# EasyEDA-wega-mixer.net
KiCad netlist of a schematic drawn in EasyEDA
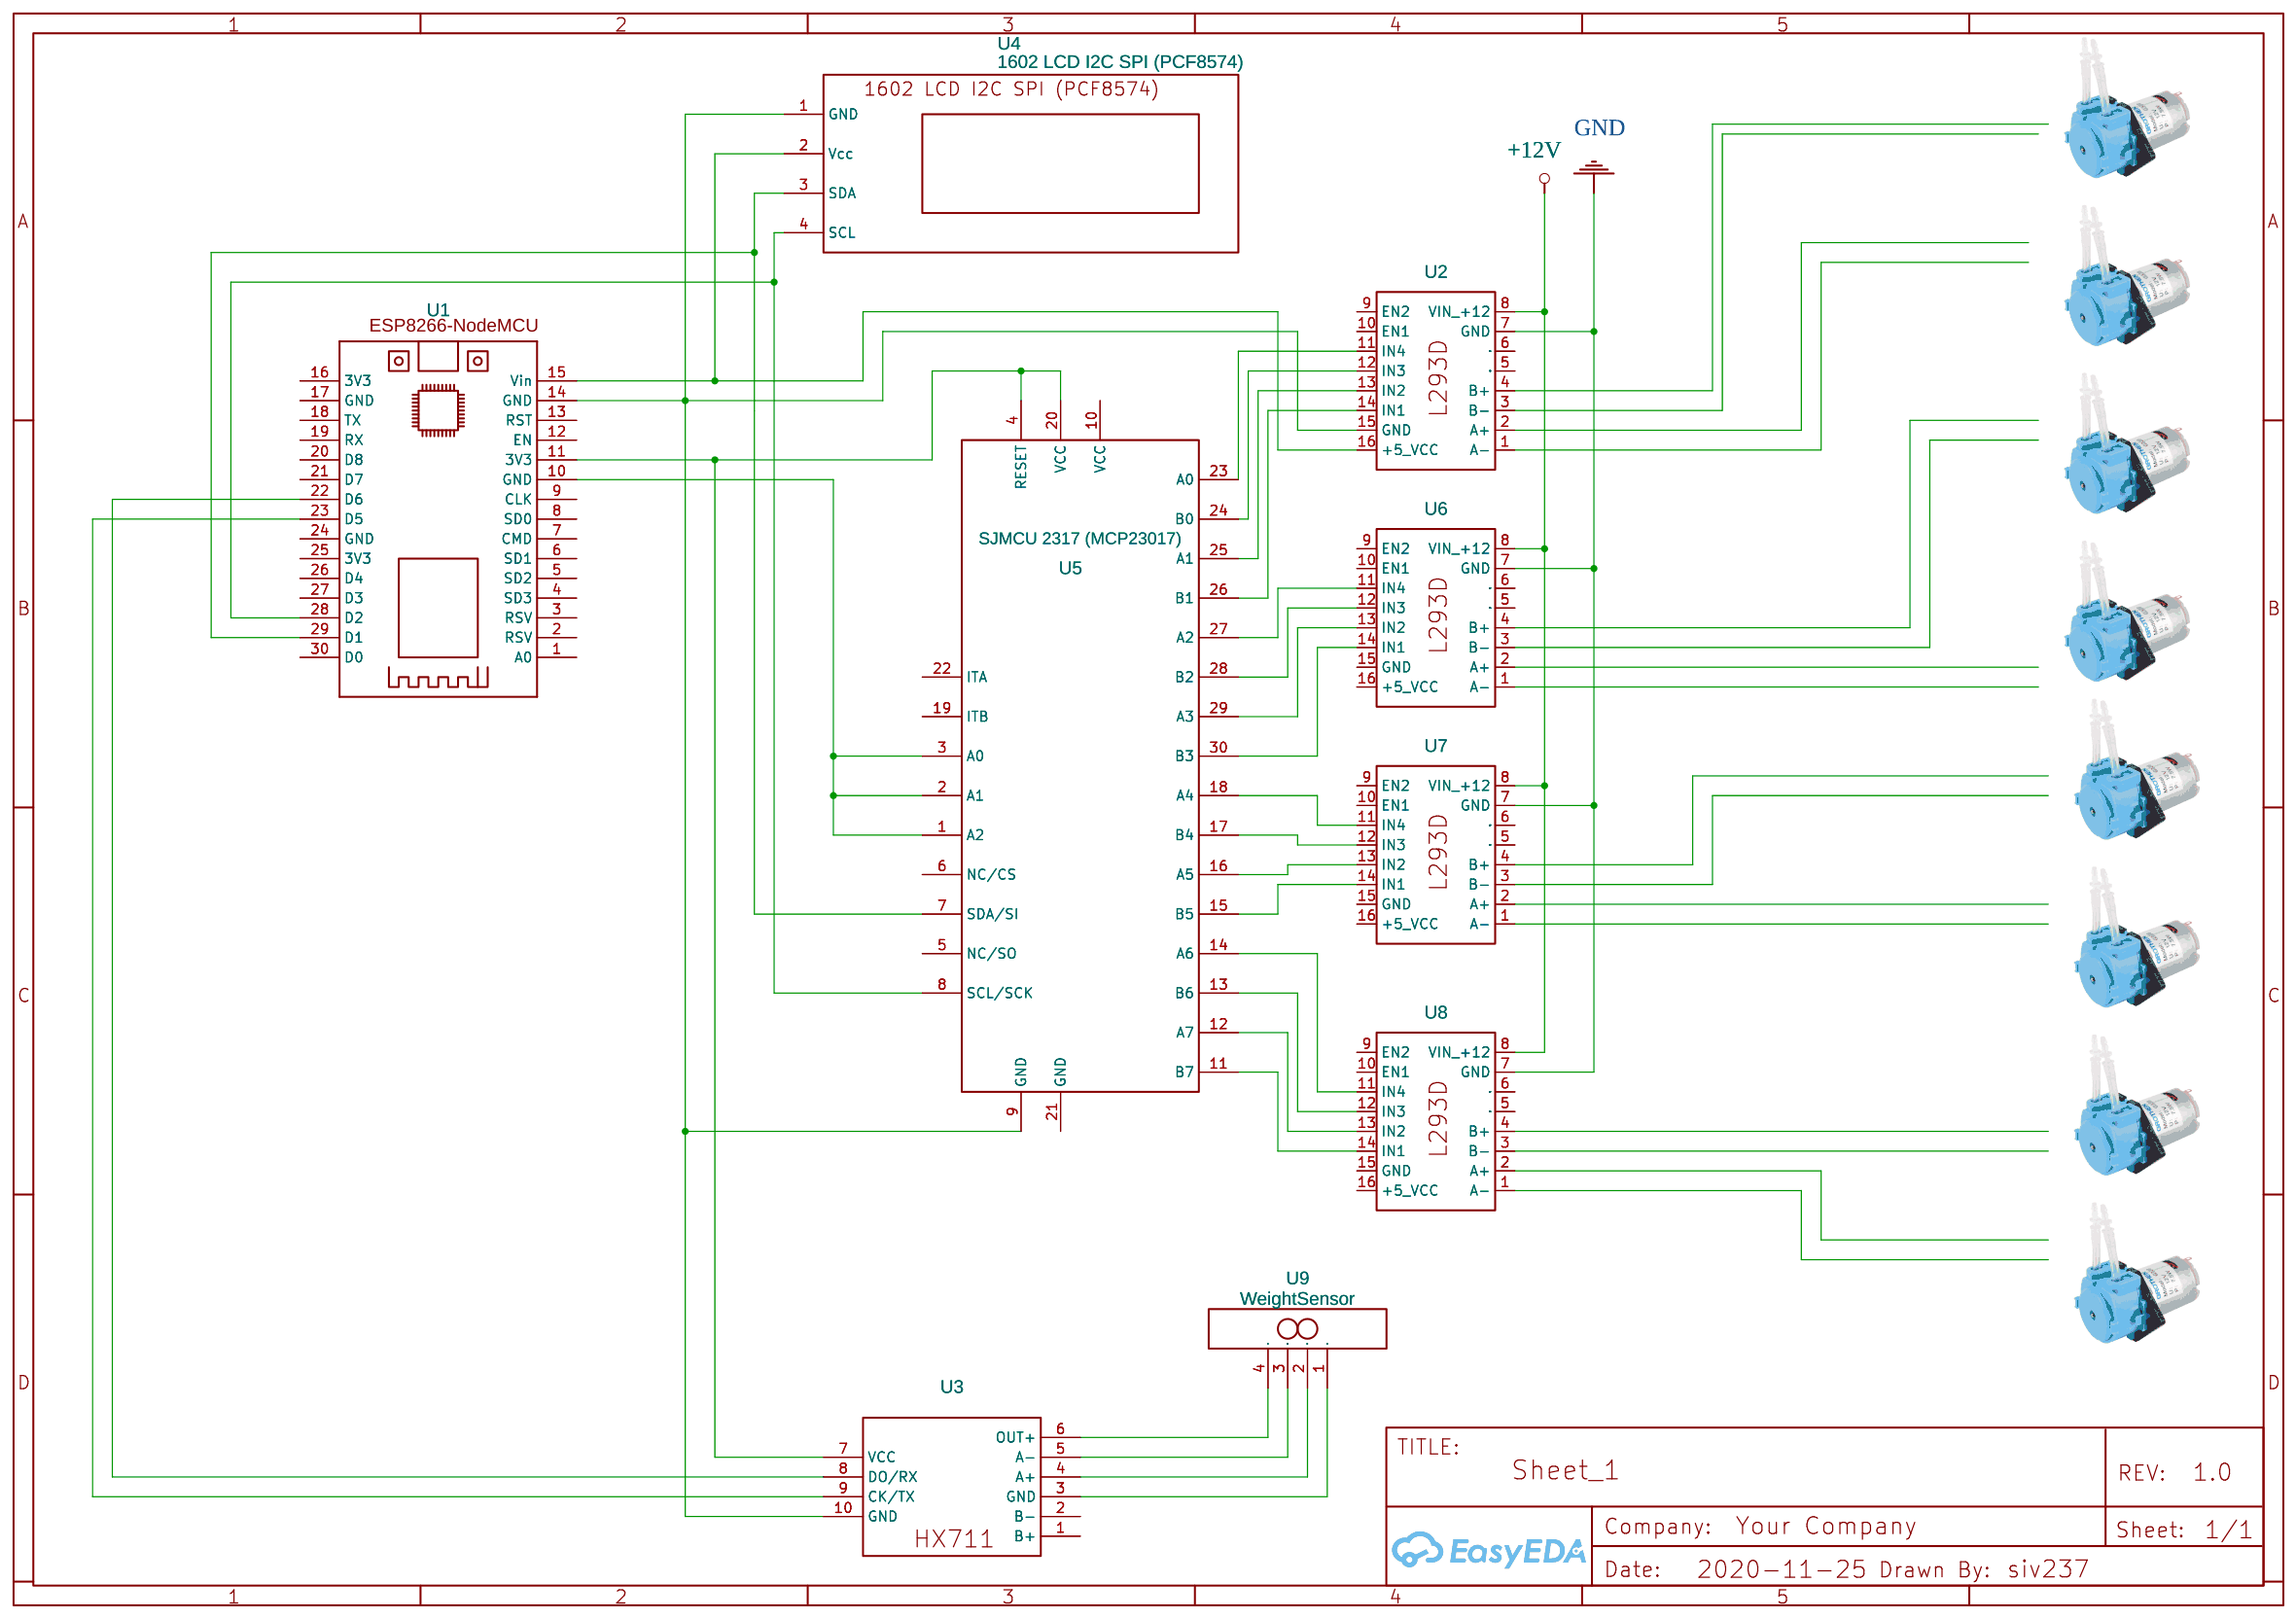
[diagram p0: schematic sheet]

(export (version "E")
  (design (tool "Eeschema 10.0.6"))
  (components
    (comp (ref "U1") (value "ESP8266 NodeMCU") (libsource (lib "") (part "ESP8266 NodeMCU")))
    (comp (ref "U2") (value "L293D") (libsource (lib "") (part "L293D")))
    (comp (ref "U3") (value "HX711") (libsource (lib "") (part "HX711")))
    (comp (ref "U4")
      (value "1602 LCD I2C SPI (PCF8574)")
      (libsource (lib "") (part "1602 LCD I2C SPI (PCF8574)"))
    )
    (comp (ref "U5") (value "SJMCU 2317 (MCP23017)") (libsource (lib "") (part "MCP23S17 Module")))
    (comp (ref "U6") (value "L293D") (libsource (lib "") (part "L293D")))
    (comp (ref "U7") (value "L293D") (libsource (lib "") (part "L293D")))
    (comp (ref "U8") (value "L293D") (libsource (lib "") (part "L293D")))
    (comp (ref "U9")
      (value "WeightSensor")
      (fields (field (name "BOM_Manufacturer Part") "New SchematicLib"))
      (libsource (lib "") (part "WeightSensor"))
    )
  )
  (nets
    (net (code "1") (name "+12V") (class "Default")
      (node (ref "U2") (pin "8") (pinfunction "VIN_+12_8") (pintype "unspecified"))
      (node (ref "U6") (pin "8") (pinfunction "VIN_+12_8") (pintype "unspecified"))
      (node (ref "U7") (pin "8") (pinfunction "VIN_+12_8") (pintype "unspecified"))
      (node (ref "U8") (pin "8") (pinfunction "VIN_+12_8") (pintype "unspecified"))
    )
    (net (code "2") (name "GND") (class "Default")
      (node (ref "U2") (pin "7") (pinfunction "GND_7") (pintype "unspecified"))
      (node (ref "U6") (pin "7") (pinfunction "GND_7") (pintype "unspecified"))
      (node (ref "U7") (pin "7") (pinfunction "GND_7") (pintype "unspecified"))
      (node (ref "U8") (pin "7") (pinfunction "GND_7") (pintype "unspecified"))
    )
    (net (code "3") (name "Net-(U1-D1)") (class "Default")
      (node (ref "U1") (pin "29") (pinfunction "D1_29") (pintype "unspecified"))
      (node (ref "U4") (pin "3") (pinfunction "SDA_3") (pintype "unspecified"))
      (node (ref "U5") (pin "7") (pinfunction "SDA/SI_7") (pintype "unspecified"))
    )
    (net (code "4") (name "Net-(U1-D2)") (class "Default")
      (node (ref "U1") (pin "28") (pinfunction "D2_28") (pintype "unspecified"))
      (node (ref "U4") (pin "4") (pinfunction "SCL_4") (pintype "unspecified"))
      (node (ref "U5") (pin "8") (pinfunction "SCL/SCK_8") (pintype "unspecified"))
    )
    (net (code "5") (name "Net-(U1-D5)") (class "Default")
      (node (ref "U1") (pin "23") (pinfunction "D5_23") (pintype "unspecified"))
      (node (ref "U3") (pin "9") (pinfunction "CK/TX_9") (pintype "unspecified"))
    )
    (net (code "6") (name "Net-(U1-D6)") (class "Default")
      (node (ref "U1") (pin "22") (pinfunction "D6_22") (pintype "unspecified"))
      (node (ref "U3") (pin "8") (pinfunction "DO/RX_8") (pintype "unspecified"))
    )
    (net (code "7") (name "Net-(U1-GND-Pad10)") (class "Default")
      (node (ref "U1") (pin "10") (pinfunction "GND_10") (pintype "unspecified"))
      (node (ref "U5") (pin "1") (pinfunction "A2_1") (pintype "unspecified"))
      (node (ref "U5") (pin "2") (pinfunction "A1_2") (pintype "unspecified"))
      (node (ref "U5") (pin "3") (pinfunction "A0_3") (pintype "unspecified"))
    )
    (net (code "8") (name "Net-(U1-Vin)") (class "Default")
      (node (ref "U1") (pin "15") (pinfunction "Vin_15") (pintype "unspecified"))
      (node (ref "U2") (pin "16") (pinfunction "+5_VCC_16") (pintype "unspecified"))
      (node (ref "U4") (pin "2") (pinfunction "Vcc_2") (pintype "unspecified"))
    )
    (net (code "9") (name "Net-(U2-IN1)") (class "Default")
      (node (ref "U2") (pin "14") (pinfunction "IN1_14") (pintype "unspecified"))
      (node (ref "U5") (pin "26") (pinfunction "B1_26") (pintype "unspecified"))
    )
    (net (code "10") (name "Net-(U2-IN2)") (class "Default")
      (node (ref "U2") (pin "13") (pinfunction "IN2_13") (pintype "unspecified"))
      (node (ref "U5") (pin "25") (pinfunction "A1_25") (pintype "unspecified"))
    )
    (net (code "11") (name "Net-(U2-IN3)") (class "Default")
      (node (ref "U2") (pin "12") (pinfunction "IN3_12") (pintype "unspecified"))
      (node (ref "U5") (pin "24") (pinfunction "B0_24") (pintype "unspecified"))
    )
    (net (code "12") (name "Net-(U2-IN4)") (class "Default")
      (node (ref "U2") (pin "11") (pinfunction "IN4_11") (pintype "unspecified"))
      (node (ref "U5") (pin "23") (pinfunction "A0_23") (pintype "unspecified"))
    )
    (net (code "13") (name "Net-(U3-A+)") (class "Default")
      (node (ref "U3") (pin "4") (pinfunction "A+_4") (pintype "unspecified"))
      (node (ref "U9") (pin "2") (pinfunction "2_2") (pintype "unspecified"))
    )
    (net (code "14") (name "Net-(U3-A-)") (class "Default")
      (node (ref "U3") (pin "5") (pinfunction "A-_5") (pintype "unspecified"))
      (node (ref "U9") (pin "3") (pinfunction "3_3") (pintype "unspecified"))
    )
    (net (code "15") (name "Net-(U3-GND-Pad3)") (class "Default")
      (node (ref "U3") (pin "3") (pinfunction "GND_3") (pintype "unspecified"))
      (node (ref "U9") (pin "1") (pinfunction "1_1") (pintype "unspecified"))
    )
    (net (code "16") (name "Net-(U3-OUT+)") (class "Default")
      (node (ref "U3") (pin "6") (pinfunction "OUT+_6") (pintype "unspecified"))
      (node (ref "U9") (pin "4") (pinfunction "4_4") (pintype "unspecified"))
    )
    (net (code "17") (name "Net-(U3-VCC)") (class "Default")
      (node (ref "U1") (pin "11") (pinfunction "3V3_11") (pintype "unspecified"))
      (node (ref "U3") (pin "7") (pinfunction "VCC_7") (pintype "unspecified"))
      (node (ref "U5") (pin "20") (pinfunction "VCC_20") (pintype "unspecified"))
      (node (ref "U5") (pin "4") (pinfunction "RESET_4") (pintype "unspecified"))
    )
    (net (code "18") (name "Net-(U4-GND)") (class "Default")
      (node (ref "U1") (pin "14") (pinfunction "GND_14") (pintype "unspecified"))
      (node (ref "U2") (pin "15") (pinfunction "GND_15") (pintype "unspecified"))
      (node (ref "U3") (pin "10") (pinfunction "GND_10") (pintype "unspecified"))
      (node (ref "U4") (pin "1") (pinfunction "GND_1") (pintype "unspecified"))
      (node (ref "U5") (pin "9") (pinfunction "GND_9") (pintype "unspecified"))
    )
    (net (code "19") (name "Net-(U5-A3)") (class "Default")
      (node (ref "U5") (pin "29") (pinfunction "A3_29") (pintype "unspecified"))
      (node (ref "U6") (pin "13") (pinfunction "IN2_13") (pintype "unspecified"))
    )
    (net (code "20") (name "Net-(U5-A4)") (class "Default")
      (node (ref "U5") (pin "18") (pinfunction "A4_18") (pintype "unspecified"))
      (node (ref "U7") (pin "11") (pinfunction "IN4_11") (pintype "unspecified"))
    )
    (net (code "21") (name "Net-(U5-A5)") (class "Default")
      (node (ref "U5") (pin "16") (pinfunction "A5_16") (pintype "unspecified"))
      (node (ref "U7") (pin "13") (pinfunction "IN2_13") (pintype "unspecified"))
    )
    (net (code "22") (name "Net-(U5-A6)") (class "Default")
      (node (ref "U5") (pin "14") (pinfunction "A6_14") (pintype "unspecified"))
      (node (ref "U8") (pin "11") (pinfunction "IN4_11") (pintype "unspecified"))
    )
    (net (code "23") (name "Net-(U5-A7)") (class "Default")
      (node (ref "U5") (pin "12") (pinfunction "A7_12") (pintype "unspecified"))
      (node (ref "U8") (pin "13") (pinfunction "IN2_13") (pintype "unspecified"))
    )
    (net (code "24") (name "Net-(U5-B2)") (class "Default")
      (node (ref "U5") (pin "28") (pinfunction "B2_28") (pintype "unspecified"))
      (node (ref "U6") (pin "12") (pinfunction "IN3_12") (pintype "unspecified"))
    )
    (net (code "25") (name "Net-(U5-B3)") (class "Default")
      (node (ref "U5") (pin "30") (pinfunction "B3_30") (pintype "unspecified"))
      (node (ref "U6") (pin "14") (pinfunction "IN1_14") (pintype "unspecified"))
    )
    (net (code "26") (name "Net-(U5-B4)") (class "Default")
      (node (ref "U5") (pin "17") (pinfunction "B4_17") (pintype "unspecified"))
      (node (ref "U7") (pin "12") (pinfunction "IN3_12") (pintype "unspecified"))
    )
    (net (code "27") (name "Net-(U5-B5)") (class "Default")
      (node (ref "U5") (pin "15") (pinfunction "B5_15") (pintype "unspecified"))
      (node (ref "U7") (pin "14") (pinfunction "IN1_14") (pintype "unspecified"))
    )
    (net (code "28") (name "Net-(U5-B6)") (class "Default")
      (node (ref "U5") (pin "13") (pinfunction "B6_13") (pintype "unspecified"))
      (node (ref "U8") (pin "12") (pinfunction "IN3_12") (pintype "unspecified"))
    )
    (net (code "29") (name "Net-(U5-B7)") (class "Default")
      (node (ref "U5") (pin "11") (pinfunction "B7_11") (pintype "unspecified"))
      (node (ref "U8") (pin "14") (pinfunction "IN1_14") (pintype "unspecified"))
    )
    (net (code "30") (name "Net-(U6-IN4)") (class "Default")
      (node (ref "U5") (pin "27") (pinfunction "A2_27") (pintype "unspecified"))
      (node (ref "U6") (pin "11") (pinfunction "IN4_11") (pintype "unspecified"))
    )
    (net (code "31") (name "unconnected-(U1-3V3-Pad16)") (class "Default")
      (node (ref "U1") (pin "16") (pinfunction "3V3_16") (pintype "unspecified"))
    )
    (net (code "32") (name "unconnected-(U1-3V3-Pad25)") (class "Default")
      (node (ref "U1") (pin "25") (pinfunction "3V3_25") (pintype "unspecified"))
    )
    (net (code "33") (name "unconnected-(U1-A0-Pad1)") (class "Default")
      (node (ref "U1") (pin "1") (pinfunction "A0_1") (pintype "unspecified"))
    )
    (net (code "34") (name "unconnected-(U1-CLK-Pad9)") (class "Default")
      (node (ref "U1") (pin "9") (pinfunction "CLK_9") (pintype "unspecified"))
    )
    (net (code "35") (name "unconnected-(U1-CMD-Pad7)") (class "Default")
      (node (ref "U1") (pin "7") (pinfunction "CMD_7") (pintype "unspecified"))
    )
    (net (code "36") (name "unconnected-(U1-D0-Pad30)") (class "Default")
      (node (ref "U1") (pin "30") (pinfunction "D0_30") (pintype "unspecified"))
    )
    (net (code "37") (name "unconnected-(U1-D3-Pad27)") (class "Default")
      (node (ref "U1") (pin "27") (pinfunction "D3_27") (pintype "unspecified"))
    )
    (net (code "38") (name "unconnected-(U1-D4-Pad26)") (class "Default")
      (node (ref "U1") (pin "26") (pinfunction "D4_26") (pintype "unspecified"))
    )
    (net (code "39") (name "unconnected-(U1-D7-Pad21)") (class "Default")
      (node (ref "U1") (pin "21") (pinfunction "D7_21") (pintype "unspecified"))
    )
    (net (code "40") (name "unconnected-(U1-D8-Pad20)") (class "Default")
      (node (ref "U1") (pin "20") (pinfunction "D8_20") (pintype "unspecified"))
    )
    (net (code "41") (name "unconnected-(U1-EN-Pad12)") (class "Default")
      (node (ref "U1") (pin "12") (pinfunction "EN_12") (pintype "unspecified"))
    )
    (net (code "42") (name "unconnected-(U1-GND-Pad17)") (class "Default")
      (node (ref "U1") (pin "17") (pinfunction "GND_17") (pintype "unspecified"))
    )
    (net (code "43") (name "unconnected-(U1-GND-Pad24)") (class "Default")
      (node (ref "U1") (pin "24") (pinfunction "GND_24") (pintype "unspecified"))
    )
    (net (code "44") (name "unconnected-(U1-RST-Pad13)") (class "Default")
      (node (ref "U1") (pin "13") (pinfunction "RST_13") (pintype "unspecified"))
    )
    (net (code "45") (name "unconnected-(U1-RSV-Pad2)") (class "Default")
      (node (ref "U1") (pin "2") (pinfunction "RSV_2") (pintype "unspecified"))
    )
    (net (code "46") (name "unconnected-(U1-RSV-Pad3)") (class "Default")
      (node (ref "U1") (pin "3") (pinfunction "RSV_3") (pintype "unspecified"))
    )
    (net (code "47") (name "unconnected-(U1-RX-Pad19)") (class "Default")
      (node (ref "U1") (pin "19") (pinfunction "RX_19") (pintype "unspecified"))
    )
    (net (code "48") (name "unconnected-(U1-SD0-Pad8)") (class "Default")
      (node (ref "U1") (pin "8") (pinfunction "SD0_8") (pintype "unspecified"))
    )
    (net (code "49") (name "unconnected-(U1-SD1-Pad6)") (class "Default")
      (node (ref "U1") (pin "6") (pinfunction "SD1_6") (pintype "unspecified"))
    )
    (net (code "50") (name "unconnected-(U1-SD2-Pad5)") (class "Default")
      (node (ref "U1") (pin "5") (pinfunction "SD2_5") (pintype "unspecified"))
    )
    (net (code "51") (name "unconnected-(U1-SD3-Pad4)") (class "Default")
      (node (ref "U1") (pin "4") (pinfunction "SD3_4") (pintype "unspecified"))
    )
    (net (code "52") (name "unconnected-(U1-TX-Pad18)") (class "Default")
      (node (ref "U1") (pin "18") (pinfunction "TX_18") (pintype "unspecified"))
    )
    (net (code "53") (name "unconnected-(U2-A+-Pad2)") (class "Default")
      (node (ref "U2") (pin "2") (pinfunction "A+_2") (pintype "unspecified"))
    )
    (net (code "54") (name "unconnected-(U2-A--Pad1)") (class "Default")
      (node (ref "U2") (pin "1") (pinfunction "A-_1") (pintype "unspecified"))
    )
    (net (code "55") (name "unconnected-(U2-B+-Pad4)") (class "Default")
      (node (ref "U2") (pin "4") (pinfunction "B+_4") (pintype "unspecified"))
    )
    (net (code "56") (name "unconnected-(U2-B--Pad3)") (class "Default")
      (node (ref "U2") (pin "3") (pinfunction "B-_3") (pintype "unspecified"))
    )
    (net (code "57") (name "unconnected-(U2-EN1-Pad10)") (class "Default")
      (node (ref "U2") (pin "10") (pinfunction "EN1_10") (pintype "unspecified"))
    )
    (net (code "58") (name "unconnected-(U2-EN2-Pad9)") (class "Default")
      (node (ref "U2") (pin "9") (pinfunction "EN2_9") (pintype "unspecified"))
    )
    (net (code "59") (name "unconnected-(U2-GND-Pad5)") (class "Default")
      (node (ref "U2") (pin "5") (pinfunction "GND_5") (pintype "unspecified"))
    )
    (net (code "60") (name "unconnected-(U2-OUT2-Pad6)") (class "Default")
      (node (ref "U2") (pin "6") (pinfunction "OUT2_6") (pintype "unspecified"))
    )
    (net (code "61") (name "unconnected-(U3-B+-Pad1)") (class "Default")
      (node (ref "U3") (pin "1") (pinfunction "B+_1") (pintype "unspecified"))
    )
    (net (code "62") (name "unconnected-(U3-B--Pad2)") (class "Default")
      (node (ref "U3") (pin "2") (pinfunction "B-_2") (pintype "unspecified"))
    )
    (net (code "63") (name "unconnected-(U5-GND-Pad21)") (class "Default")
      (node (ref "U5") (pin "21") (pinfunction "GND_21") (pintype "unspecified"))
    )
    (net (code "64") (name "unconnected-(U5-ITA-Pad22)") (class "Default")
      (node (ref "U5") (pin "22") (pinfunction "ITA_22") (pintype "unspecified"))
    )
    (net (code "65") (name "unconnected-(U5-ITB-Pad19)") (class "Default")
      (node (ref "U5") (pin "19") (pinfunction "ITB_19") (pintype "unspecified"))
    )
    (net (code "66") (name "unconnected-(U5-NC{slash}CS-Pad6)") (class "Default")
      (node (ref "U5") (pin "6") (pinfunction "NC/CS_6") (pintype "unspecified"))
    )
    (net (code "67") (name "unconnected-(U5-NC{slash}SO-Pad5)") (class "Default")
      (node (ref "U5") (pin "5") (pinfunction "NC/SO_5") (pintype "unspecified"))
    )
    (net (code "68") (name "unconnected-(U5-VCC-Pad10)") (class "Default")
      (node (ref "U5") (pin "10") (pinfunction "VCC_10") (pintype "unspecified"))
    )
    (net (code "69") (name "unconnected-(U6-+5_VCC-Pad16)") (class "Default")
      (node (ref "U6") (pin "16") (pinfunction "+5_VCC_16") (pintype "unspecified"))
    )
    (net (code "70") (name "unconnected-(U6-A+-Pad2)") (class "Default")
      (node (ref "U6") (pin "2") (pinfunction "A+_2") (pintype "unspecified"))
    )
    (net (code "71") (name "unconnected-(U6-A--Pad1)") (class "Default")
      (node (ref "U6") (pin "1") (pinfunction "A-_1") (pintype "unspecified"))
    )
    (net (code "72") (name "unconnected-(U6-B+-Pad4)") (class "Default")
      (node (ref "U6") (pin "4") (pinfunction "B+_4") (pintype "unspecified"))
    )
    (net (code "73") (name "unconnected-(U6-B--Pad3)") (class "Default")
      (node (ref "U6") (pin "3") (pinfunction "B-_3") (pintype "unspecified"))
    )
    (net (code "74") (name "unconnected-(U6-EN1-Pad10)") (class "Default")
      (node (ref "U6") (pin "10") (pinfunction "EN1_10") (pintype "unspecified"))
    )
    (net (code "75") (name "unconnected-(U6-EN2-Pad9)") (class "Default")
      (node (ref "U6") (pin "9") (pinfunction "EN2_9") (pintype "unspecified"))
    )
    (net (code "76") (name "unconnected-(U6-GND-Pad5)") (class "Default")
      (node (ref "U6") (pin "5") (pinfunction "GND_5") (pintype "unspecified"))
    )
    (net (code "77") (name "unconnected-(U6-GND-Pad15)") (class "Default")
      (node (ref "U6") (pin "15") (pinfunction "GND_15") (pintype "unspecified"))
    )
    (net (code "78") (name "unconnected-(U6-OUT2-Pad6)") (class "Default")
      (node (ref "U6") (pin "6") (pinfunction "OUT2_6") (pintype "unspecified"))
    )
    (net (code "79") (name "unconnected-(U7-+5_VCC-Pad16)") (class "Default")
      (node (ref "U7") (pin "16") (pinfunction "+5_VCC_16") (pintype "unspecified"))
    )
    (net (code "80") (name "unconnected-(U7-A+-Pad2)") (class "Default")
      (node (ref "U7") (pin "2") (pinfunction "A+_2") (pintype "unspecified"))
    )
    (net (code "81") (name "unconnected-(U7-A--Pad1)") (class "Default")
      (node (ref "U7") (pin "1") (pinfunction "A-_1") (pintype "unspecified"))
    )
    (net (code "82") (name "unconnected-(U7-B+-Pad4)") (class "Default")
      (node (ref "U7") (pin "4") (pinfunction "B+_4") (pintype "unspecified"))
    )
    (net (code "83") (name "unconnected-(U7-B--Pad3)") (class "Default")
      (node (ref "U7") (pin "3") (pinfunction "B-_3") (pintype "unspecified"))
    )
    (net (code "84") (name "unconnected-(U7-EN1-Pad10)") (class "Default")
      (node (ref "U7") (pin "10") (pinfunction "EN1_10") (pintype "unspecified"))
    )
    (net (code "85") (name "unconnected-(U7-EN2-Pad9)") (class "Default")
      (node (ref "U7") (pin "9") (pinfunction "EN2_9") (pintype "unspecified"))
    )
    (net (code "86") (name "unconnected-(U7-GND-Pad5)") (class "Default")
      (node (ref "U7") (pin "5") (pinfunction "GND_5") (pintype "unspecified"))
    )
    (net (code "87") (name "unconnected-(U7-GND-Pad15)") (class "Default")
      (node (ref "U7") (pin "15") (pinfunction "GND_15") (pintype "unspecified"))
    )
    (net (code "88") (name "unconnected-(U7-OUT2-Pad6)") (class "Default")
      (node (ref "U7") (pin "6") (pinfunction "OUT2_6") (pintype "unspecified"))
    )
    (net (code "89") (name "unconnected-(U8-+5_VCC-Pad16)") (class "Default")
      (node (ref "U8") (pin "16") (pinfunction "+5_VCC_16") (pintype "unspecified"))
    )
    (net (code "90") (name "unconnected-(U8-A+-Pad2)") (class "Default")
      (node (ref "U8") (pin "2") (pinfunction "A+_2") (pintype "unspecified"))
    )
    (net (code "91") (name "unconnected-(U8-A--Pad1)") (class "Default")
      (node (ref "U8") (pin "1") (pinfunction "A-_1") (pintype "unspecified"))
    )
    (net (code "92") (name "unconnected-(U8-B+-Pad4)") (class "Default")
      (node (ref "U8") (pin "4") (pinfunction "B+_4") (pintype "unspecified"))
    )
    (net (code "93") (name "unconnected-(U8-B--Pad3)") (class "Default")
      (node (ref "U8") (pin "3") (pinfunction "B-_3") (pintype "unspecified"))
    )
    (net (code "94") (name "unconnected-(U8-EN1-Pad10)") (class "Default")
      (node (ref "U8") (pin "10") (pinfunction "EN1_10") (pintype "unspecified"))
    )
    (net (code "95") (name "unconnected-(U8-EN2-Pad9)") (class "Default")
      (node (ref "U8") (pin "9") (pinfunction "EN2_9") (pintype "unspecified"))
    )
    (net (code "96") (name "unconnected-(U8-GND-Pad5)") (class "Default")
      (node (ref "U8") (pin "5") (pinfunction "GND_5") (pintype "unspecified"))
    )
    (net (code "97") (name "unconnected-(U8-GND-Pad15)") (class "Default")
      (node (ref "U8") (pin "15") (pinfunction "GND_15") (pintype "unspecified"))
    )
    (net (code "98") (name "unconnected-(U8-OUT2-Pad6)") (class "Default")
      (node (ref "U8") (pin "6") (pinfunction "OUT2_6") (pintype "unspecified"))
    )
  )
)
